# design.net
KiCad netlist of a schematic drawn in Altium Designer
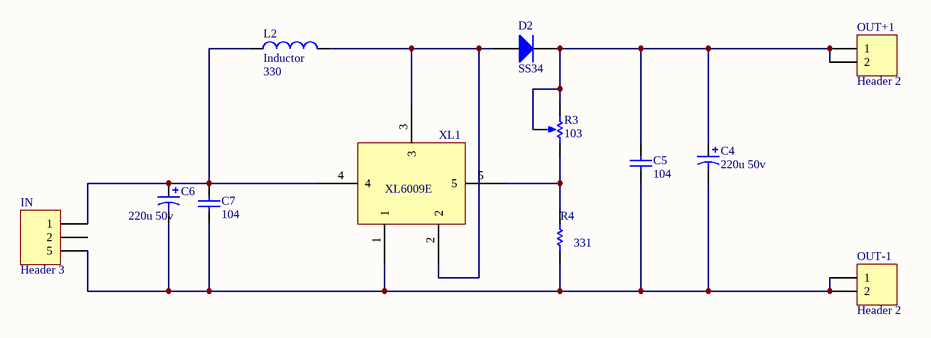
[diagram p0: 升压模块.SchDoc]

(export (version "E")
  (design (tool "Eeschema 10.0.6"))
  (components
    (comp (ref "C4")
      (value "220u 50v")
      (footprint "ABSM-1574")
      (description "Polarized Capacitor (Radial)")
      (fields (field (name "PUBLISHER") "Altium Limited"))
      (libsource (lib "Miscellaneous Devices") (part "Cap Pol1"))
    )
    (comp (ref "C5")
      (value "104")
      (footprint "C1206")
      (description "Capacitor")
      (fields (field (name "PUBLISHER") "Altium Limited"))
      (libsource (lib "Miscellaneous Devices") (part "Cap"))
    )
    (comp (ref "C6")
      (value "220u 50v")
      (footprint "ABSM-1574")
      (description "Polarized Capacitor (Radial)")
      (fields (field (name "PUBLISHER") "Altium Limited"))
      (libsource (lib "Miscellaneous Devices") (part "Cap Pol1"))
    )
    (comp (ref "C7")
      (value "104")
      (footprint "C1206")
      (description "Capacitor")
      (fields (field (name "PUBLISHER") "Altium Limited"))
      (libsource (lib "Miscellaneous Devices") (part "Cap"))
    )
    (comp (ref "D2")
      (value "SS34")
      (footprint "SMC")
      (description "Default Diode")
      (fields (field (name "PUBLISHER") "Altium Limited"))
      (libsource (lib "Miscellaneous Devices") (part "Diode"))
    )
    (comp (ref "IN")
      (value "Header 3")
      (footprint "HDR1X5")
      (description "Header, 3-Pin")
      (fields (field (name "PUBLISHER") "Altium Limited"))
      (libsource (lib "Miscellaneous Connectors") (part "Header 3"))
    )
    (comp (ref "L2")
      (value "Inductor")
      (footprint "l")
      (fields (field (name "ALTIUM_VALUE") "330") (field (name "PUBLISHER") "Altium Limited"))
      (libsource (lib "Miscellaneous Devices") (part "Inductor"))
    )
    (comp (ref "OUT+1")
      (value "Header 2")
      (footprint "HDR2X2")
      (description "Header, 2-Pin")
      (fields (field (name "PUBLISHER") "Altium Limited"))
      (libsource (lib "Miscellaneous Connectors") (part "Header 2"))
    )
    (comp (ref "OUT-1")
      (value "Header 2")
      (footprint "HDR2X2")
      (description "Header, 2-Pin")
      (fields (field (name "PUBLISHER") "Altium Limited"))
      (libsource (lib "Miscellaneous Connectors") (part "Header 2"))
    )
    (comp (ref "R3")
      (value "103")
      (footprint "HDR1X3")
      (description "Potentiometer")
      (fields (field (name "PUBLISHER") "Altium Limited"))
      (libsource (lib "Miscellaneous Devices") (part "RPot"))
    )
    (comp (ref "R4")
      (value "331")
      (footprint "C1206")
      (description "Resistor")
      (fields (field (name "PUBLISHER") "Altium Limited"))
      (libsource (lib "Miscellaneous Devices") (part "Res1"))
    )
    (comp (ref "XL1") (value "XL6009e") (footprint "d2") (libsource (lib "*") (part "XL6009e")))
  )
  (nets
    (net (code "1") (name "Net-(C4-Pad2)") (class "Default")
      (node (ref "C4") (pin "2") (pinfunction "2_2") (pintype "passive"))
      (node (ref "C5") (pin "1") (pinfunction "1_1") (pintype "passive"))
      (node (ref "C6") (pin "2") (pinfunction "2_2") (pintype "passive"))
      (node (ref "C7") (pin "1") (pinfunction "1_1") (pintype "passive"))
      (node (ref "IN") (pin "5") (pinfunction "5_5") (pintype "passive"))
      (node (ref "OUT-1") (pin "1") (pinfunction "1_1") (pintype "passive"))
      (node (ref "OUT-1") (pin "2") (pinfunction "2_2") (pintype "passive"))
      (node (ref "R4") (pin "1") (pinfunction "1_1") (pintype "passive"))
      (node (ref "XL1") (pin "1") (pinfunction "1_1") (pintype "passive"))
    )
    (net (code "2") (name "Net-(C6-Pad1)") (class "Default")
      (node (ref "C6") (pin "1") (pinfunction "1_1") (pintype "passive"))
      (node (ref "C7") (pin "2") (pinfunction "2_2") (pintype "passive"))
      (node (ref "IN") (pin "1") (pinfunction "1_1") (pintype "passive"))
      (node (ref "L2") (pin "1") (pinfunction "1_1") (pintype "passive"))
      (node (ref "XL1") (pin "4") (pinfunction "4_4") (pintype "passive"))
    )
    (net (code "3") (name "Net-(D2-A)") (class "Default")
      (node (ref "D2") (pin "1") (pinfunction "A_1") (pintype "passive"))
      (node (ref "L2") (pin "0") (pinfunction "0_0") (pintype "passive"))
      (node (ref "XL1") (pin "2") (pinfunction "2_2") (pintype "passive"))
      (node (ref "XL1") (pin "3") (pinfunction "3_3") (pintype "passive"))
    )
    (net (code "4") (name "Net-(D2-K)") (class "Default")
      (node (ref "C4") (pin "1") (pinfunction "1_1") (pintype "passive"))
      (node (ref "C5") (pin "2") (pinfunction "2_2") (pintype "passive"))
      (node (ref "D2") (pin "2") (pinfunction "K_2") (pintype "passive"))
      (node (ref "OUT+1") (pin "1") (pinfunction "1_1") (pintype "passive"))
      (node (ref "OUT+1") (pin "2") (pinfunction "2_2") (pintype "passive"))
      (node (ref "R3") (pin "2") (pinfunction "TAP_2") (pintype "passive"))
      (node (ref "R3") (pin "3") (pinfunction "TOP_3") (pintype "passive"))
    )
    (net (code "5") (name "Net-(R3-BOT)") (class "Default")
      (node (ref "R3") (pin "1") (pinfunction "BOT_1") (pintype "passive"))
      (node (ref "R4") (pin "2") (pinfunction "2_2") (pintype "passive"))
      (node (ref "XL1") (pin "5") (pinfunction "5_5") (pintype "passive"))
    )
    (net (code "6") (name "unconnected-(IN-Pad2)") (class "Default")
      (node (ref "IN") (pin "2") (pinfunction "2_2") (pintype "passive"))
    )
  )
)
